# motor_driver.net
KiCad netlist of a schematic drawn in EAGLE
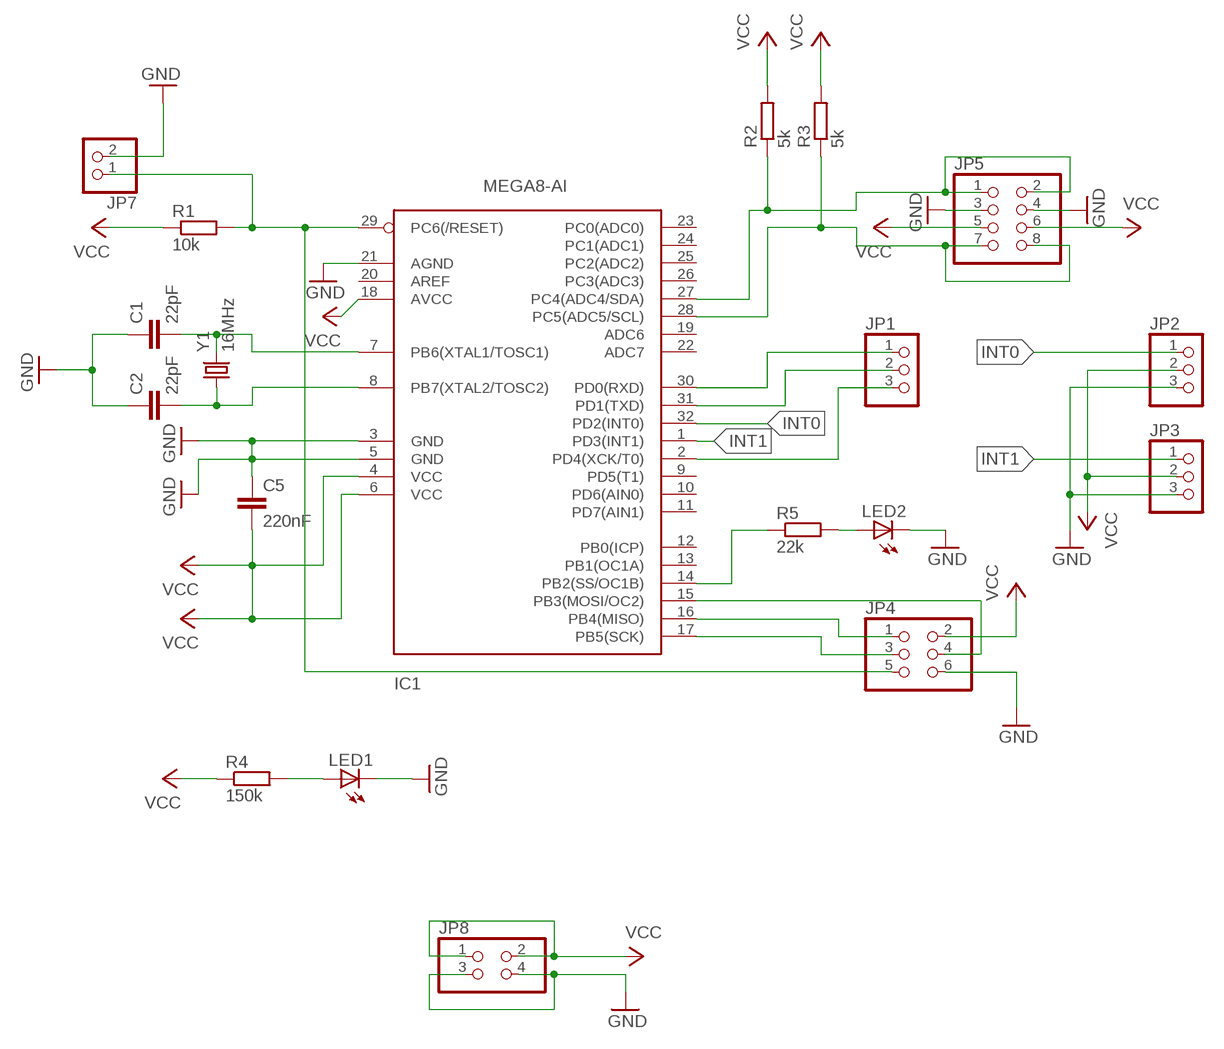
[diagram p0: schematic, sheet 1]

(export (version "E")
  (design (tool "Eeschema 10.0.6"))
  (components
    (comp (ref "C1")
      (value "22pF")
      (footprint "eagle-import:1206")
      (libsource (lib "eagle-import") (part "CAP1206"))
    )
    (comp (ref "C2")
      (value "22pF")
      (footprint "eagle-import:1206")
      (libsource (lib "eagle-import") (part "CAP1206"))
    )
    (comp (ref "C5")
      (value "220nF")
      (footprint "eagle-import:0805")
      (libsource (lib "eagle-import") (part "CAP0805"))
    )
    (comp (ref "IC1")
      (value "MEGA8-AI")
      (footprint "eagle-import:TQFP32-08")
      (libsource (lib "eagle-import") (part "MEGA8-AI"))
    )
    (comp (ref "JP1")
      (value "PINHD-1X3")
      (footprint "eagle-import:1X03")
      (libsource (lib "eagle-import") (part "PINHD-1X3"))
    )
    (comp (ref "JP2")
      (value "PINHD-1X3")
      (footprint "eagle-import:1X03")
      (libsource (lib "eagle-import") (part "PINHD-1X3"))
    )
    (comp (ref "JP3")
      (value "PINHD-1X3")
      (footprint "eagle-import:1X03")
      (libsource (lib "eagle-import") (part "PINHD-1X3"))
    )
    (comp (ref "JP4")
      (value "PINHD-2X3")
      (footprint "eagle-import:2X03")
      (libsource (lib "eagle-import") (part "PINHD-2X3"))
    )
    (comp (ref "JP5")
      (value "PINHD-2X4")
      (footprint "eagle-import:2X04")
      (libsource (lib "eagle-import") (part "PINHD-2X4"))
    )
    (comp (ref "JP7")
      (value "PINHD-1X2")
      (footprint "eagle-import:1X02")
      (libsource (lib "eagle-import") (part "PINHD-1X2"))
    )
    (comp (ref "JP8")
      (value "PINHD-2X2")
      (footprint "eagle-import:2X02")
      (libsource (lib "eagle-import") (part "PINHD-2X2"))
    )
    (comp (ref "LED1")
      (value "LEDCHIPLED_0805")
      (footprint "eagle-import:CHIPLED_0805")
      (libsource (lib "eagle-import") (part "LEDCHIPLED_0805"))
    )
    (comp (ref "LED2")
      (value "LEDCHIPLED_0805")
      (footprint "eagle-import:CHIPLED_0805")
      (libsource (lib "eagle-import") (part "LEDCHIPLED_0805"))
    )
    (comp (ref "R1")
      (value "10k")
      (footprint "eagle-import:R1206")
      (libsource (lib "eagle-import") (part "RR1206"))
    )
    (comp (ref "R2")
      (value "5k")
      (footprint "eagle-import:R1206")
      (libsource (lib "eagle-import") (part "RR1206"))
    )
    (comp (ref "R3")
      (value "5k")
      (footprint "eagle-import:R1206")
      (libsource (lib "eagle-import") (part "RR1206"))
    )
    (comp (ref "R4")
      (value "150k")
      (footprint "eagle-import:R0805")
      (libsource (lib "eagle-import") (part "R"))
    )
    (comp (ref "R5")
      (value "22k")
      (footprint "eagle-import:R0805")
      (libsource (lib "eagle-import") (part "R"))
    )
    (comp (ref "Y1")
      (value "16MHz")
      (footprint "eagle-import:HC49UP")
      (libsource (lib "eagle-import") (part "CRYSTALSMD"))
    )
  )
  (nets
    (net (code "1") (name "GND") (class "Default")
      (node (ref "C1") (pin "1") (pinfunction "1_1") (pintype "passive"))
      (node (ref "C2") (pin "1") (pinfunction "1_1") (pintype "passive"))
      (node (ref "C5") (pin "1") (pinfunction "1_1") (pintype "passive"))
      (node (ref "IC1") (pin "21") (pinfunction "AGND_21") (pintype "bidirectional"))
      (node (ref "IC1") (pin "3") (pinfunction "GND_3") (pintype "bidirectional"))
      (node (ref "IC1") (pin "5") (pinfunction "GND_5") (pintype "bidirectional"))
      (node (ref "JP2") (pin "3") (pinfunction "3_3") (pintype "passive"))
      (node (ref "JP3") (pin "3") (pinfunction "3_3") (pintype "passive"))
      (node (ref "JP4") (pin "6") (pinfunction "6_6") (pintype "passive"))
      (node (ref "JP5") (pin "3") (pinfunction "3_3") (pintype "passive"))
      (node (ref "JP5") (pin "4") (pinfunction "4_4") (pintype "passive"))
      (node (ref "JP7") (pin "2") (pinfunction "2_2") (pintype "passive"))
      (node (ref "JP8") (pin "3") (pinfunction "3_3") (pintype "passive"))
      (node (ref "JP8") (pin "4") (pinfunction "4_4") (pintype "passive"))
      (node (ref "LED1") (pin "C") (pinfunction "C_C") (pintype "passive"))
      (node (ref "LED2") (pin "C") (pinfunction "C_C") (pintype "passive"))
    )
    (net (code "2") (name "INT0") (class "Default")
      (node (ref "IC1") (pin "32") (pinfunction "PD2(INT0)_32") (pintype "bidirectional"))
      (node (ref "JP2") (pin "1") (pinfunction "1_1") (pintype "passive"))
    )
    (net (code "3") (name "INT1") (class "Default")
      (node (ref "IC1") (pin "1") (pinfunction "PD3(INT1)_1") (pintype "bidirectional"))
      (node (ref "JP3") (pin "1") (pinfunction "1_1") (pintype "passive"))
    )
    (net (code "4") (name "Net-(IC1-PB2(SS{slash}OC1B))") (class "Default")
      (node (ref "IC1") (pin "14") (pinfunction "PB2(SS/OC1B)_14") (pintype "bidirectional"))
      (node (ref "R5") (pin "1") (pinfunction "1_1") (pintype "passive"))
    )
    (net (code "5") (name "Net-(IC1-PB3(MOSI{slash}OC2))") (class "Default")
      (node (ref "IC1") (pin "15") (pinfunction "PB3(MOSI/OC2)_15") (pintype "bidirectional"))
      (node (ref "JP4") (pin "4") (pinfunction "4_4") (pintype "passive"))
    )
    (net (code "6") (name "Net-(IC1-PB4(MISO))") (class "Default")
      (node (ref "IC1") (pin "16") (pinfunction "PB4(MISO)_16") (pintype "bidirectional"))
      (node (ref "JP4") (pin "1") (pinfunction "1_1") (pintype "passive"))
    )
    (net (code "7") (name "Net-(IC1-PB5(SCK))") (class "Default")
      (node (ref "IC1") (pin "17") (pinfunction "PB5(SCK)_17") (pintype "bidirectional"))
      (node (ref "JP4") (pin "3") (pinfunction "3_3") (pintype "passive"))
    )
    (net (code "8") (name "Net-(IC1-PB6(XTAL1{slash}TOSC1))") (class "Default")
      (node (ref "C1") (pin "2") (pinfunction "2_2") (pintype "passive"))
      (node (ref "IC1") (pin "7") (pinfunction "PB6(XTAL1/TOSC1)_7") (pintype "bidirectional"))
      (node (ref "Y1") (pin "2") (pinfunction "2_2") (pintype "passive"))
    )
    (net (code "9") (name "Net-(IC1-PB7(XTAL2{slash}TOSC2))") (class "Default")
      (node (ref "C2") (pin "2") (pinfunction "2_2") (pintype "passive"))
      (node (ref "IC1") (pin "8") (pinfunction "PB7(XTAL2/TOSC2)_8") (pintype "bidirectional"))
      (node (ref "Y1") (pin "1") (pinfunction "1_1") (pintype "passive"))
    )
    (net (code "10") (name "Net-(IC1-PC4(ADC4{slash}SDA))") (class "Default")
      (node (ref "IC1") (pin "27") (pinfunction "PC4(ADC4/SDA)_27") (pintype "bidirectional"))
      (node (ref "JP5") (pin "1") (pinfunction "1_1") (pintype "passive"))
      (node (ref "JP5") (pin "2") (pinfunction "2_2") (pintype "passive"))
      (node (ref "R2") (pin "1") (pinfunction "1_1") (pintype "passive"))
    )
    (net (code "11") (name "Net-(IC1-PC5(ADC5{slash}SCL))") (class "Default")
      (node (ref "IC1") (pin "28") (pinfunction "PC5(ADC5/SCL)_28") (pintype "bidirectional"))
      (node (ref "JP5") (pin "7") (pinfunction "7_7") (pintype "passive"))
      (node (ref "JP5") (pin "8") (pinfunction "8_8") (pintype "passive"))
      (node (ref "R3") (pin "1") (pinfunction "1_1") (pintype "passive"))
    )
    (net (code "12") (name "Net-(IC1-PC6({slash}RESET))") (class "Default")
      (node (ref "IC1") (pin "29") (pinfunction "PC6(/RESET)_29") (pintype "bidirectional"))
      (node (ref "JP4") (pin "5") (pinfunction "5_5") (pintype "passive"))
      (node (ref "JP7") (pin "1") (pinfunction "1_1") (pintype "passive"))
      (node (ref "R1") (pin "2") (pinfunction "2_2") (pintype "passive"))
    )
    (net (code "13") (name "Net-(IC1-PD0(RXD))") (class "Default")
      (node (ref "IC1") (pin "30") (pinfunction "PD0(RXD)_30") (pintype "bidirectional"))
      (node (ref "JP1") (pin "1") (pinfunction "1_1") (pintype "passive"))
    )
    (net (code "14") (name "Net-(IC1-PD1(TXD))") (class "Default")
      (node (ref "IC1") (pin "31") (pinfunction "PD1(TXD)_31") (pintype "bidirectional"))
      (node (ref "JP1") (pin "2") (pinfunction "2_2") (pintype "passive"))
    )
    (net (code "15") (name "Net-(IC1-PD4(XCK{slash}T0))") (class "Default")
      (node (ref "IC1") (pin "2") (pinfunction "PD4(XCK/T0)_2") (pintype "bidirectional"))
      (node (ref "JP1") (pin "3") (pinfunction "3_3") (pintype "passive"))
    )
    (net (code "16") (name "Net-(LED1-PadA)") (class "Default")
      (node (ref "LED1") (pin "A") (pinfunction "A_A") (pintype "passive"))
      (node (ref "R4") (pin "2") (pinfunction "2_2") (pintype "passive"))
    )
    (net (code "17") (name "Net-(LED2-PadA)") (class "Default")
      (node (ref "LED2") (pin "A") (pinfunction "A_A") (pintype "passive"))
      (node (ref "R5") (pin "2") (pinfunction "2_2") (pintype "passive"))
    )
    (net (code "18") (name "VCC") (class "Default")
      (node (ref "C5") (pin "2") (pinfunction "2_2") (pintype "passive"))
      (node (ref "IC1") (pin "18") (pinfunction "AVCC_18") (pintype "bidirectional"))
      (node (ref "IC1") (pin "4") (pinfunction "VCC_4") (pintype "bidirectional"))
      (node (ref "IC1") (pin "6") (pinfunction "VCC_6") (pintype "bidirectional"))
      (node (ref "JP2") (pin "2") (pinfunction "2_2") (pintype "passive"))
      (node (ref "JP3") (pin "2") (pinfunction "2_2") (pintype "passive"))
      (node (ref "JP4") (pin "2") (pinfunction "2_2") (pintype "passive"))
      (node (ref "JP5") (pin "5") (pinfunction "5_5") (pintype "passive"))
      (node (ref "JP5") (pin "6") (pinfunction "6_6") (pintype "passive"))
      (node (ref "JP8") (pin "1") (pinfunction "1_1") (pintype "passive"))
      (node (ref "JP8") (pin "2") (pinfunction "2_2") (pintype "passive"))
      (node (ref "R1") (pin "1") (pinfunction "1_1") (pintype "passive"))
      (node (ref "R2") (pin "2") (pinfunction "2_2") (pintype "passive"))
      (node (ref "R3") (pin "2") (pinfunction "2_2") (pintype "passive"))
      (node (ref "R4") (pin "1") (pinfunction "1_1") (pintype "passive"))
    )
    (net (code "19") (name "unconnected-(IC1-ADC6-Pad19)") (class "Default")
      (node (ref "IC1") (pin "19") (pinfunction "ADC6_19") (pintype "bidirectional"))
    )
    (net (code "20") (name "unconnected-(IC1-ADC7-Pad22)") (class "Default")
      (node (ref "IC1") (pin "22") (pinfunction "ADC7_22") (pintype "bidirectional"))
    )
    (net (code "21") (name "unconnected-(IC1-AREF-Pad20)") (class "Default")
      (node (ref "IC1") (pin "20") (pinfunction "AREF_20") (pintype "bidirectional"))
    )
    (net (code "22") (name "unconnected-(IC1-PB0(ICP)-Pad12)") (class "Default")
      (node (ref "IC1") (pin "12") (pinfunction "PB0(ICP)_12") (pintype "bidirectional"))
    )
    (net (code "23") (name "unconnected-(IC1-PB1(OC1A)-Pad13)") (class "Default")
      (node (ref "IC1") (pin "13") (pinfunction "PB1(OC1A)_13") (pintype "bidirectional"))
    )
    (net (code "24") (name "unconnected-(IC1-PC0(ADC0)-Pad23)") (class "Default")
      (node (ref "IC1") (pin "23") (pinfunction "PC0(ADC0)_23") (pintype "bidirectional"))
    )
    (net (code "25") (name "unconnected-(IC1-PC1(ADC1)-Pad24)") (class "Default")
      (node (ref "IC1") (pin "24") (pinfunction "PC1(ADC1)_24") (pintype "bidirectional"))
    )
    (net (code "26") (name "unconnected-(IC1-PC2(ADC2)-Pad25)") (class "Default")
      (node (ref "IC1") (pin "25") (pinfunction "PC2(ADC2)_25") (pintype "bidirectional"))
    )
    (net (code "27") (name "unconnected-(IC1-PC3(ADC3)-Pad26)") (class "Default")
      (node (ref "IC1") (pin "26") (pinfunction "PC3(ADC3)_26") (pintype "bidirectional"))
    )
    (net (code "28") (name "unconnected-(IC1-PD5(T1)-Pad9)") (class "Default")
      (node (ref "IC1") (pin "9") (pinfunction "PD5(T1)_9") (pintype "bidirectional"))
    )
    (net (code "29") (name "unconnected-(IC1-PD6(AIN0)-Pad10)") (class "Default")
      (node (ref "IC1") (pin "10") (pinfunction "PD6(AIN0)_10") (pintype "bidirectional"))
    )
    (net (code "30") (name "unconnected-(IC1-PD7(AIN1)-Pad11)") (class "Default")
      (node (ref "IC1") (pin "11") (pinfunction "PD7(AIN1)_11") (pintype "bidirectional"))
    )
  )
)
